# Passive_KLine.net
KiCad netlist of a schematic drawn in EAGLE
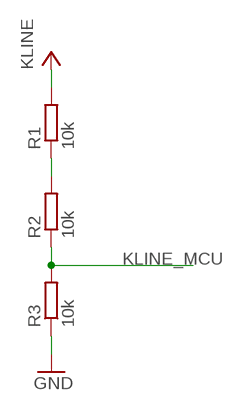
[diagram p0: schematic, sheet 1]

(export (version "E")
  (design (tool "Eeschema 10.0.6"))
  (components
    (comp (ref "R1")
      (value "10k")
      (footprint "eagle-import:R1206")
      (libsource (lib "eagle-import") (part "R-EU_R1206"))
    )
    (comp (ref "R2")
      (value "10k")
      (footprint "eagle-import:R1206")
      (libsource (lib "eagle-import") (part "R-EU_R1206"))
    )
    (comp (ref "R3")
      (value "10k")
      (footprint "eagle-import:R1206")
      (libsource (lib "eagle-import") (part "R-EU_R1206"))
    )
  )
  (nets
    (net (code "1") (name "/KLINE_MCU") (class "Default")
      (node (ref "R2") (pin "1") (pinfunction "1_1") (pintype "passive"))
      (node (ref "R3") (pin "2") (pinfunction "2_2") (pintype "passive"))
    )
    (net (code "2") (name "GND") (class "Default")
      (node (ref "R3") (pin "1") (pinfunction "1_1") (pintype "passive"))
    )
    (net (code "3") (name "KLINE") (class "Default")
      (node (ref "R1") (pin "2") (pinfunction "2_2") (pintype "passive"))
    )
    (net (code "4") (name "Net-(R1-Pad1)") (class "Default")
      (node (ref "R1") (pin "1") (pinfunction "1_1") (pintype "passive"))
      (node (ref "R2") (pin "2") (pinfunction "2_2") (pintype "passive"))
    )
  )
)
